# SCH_d_01_e_03.net
KiCad netlist of a schematic drawn in EasyEDA
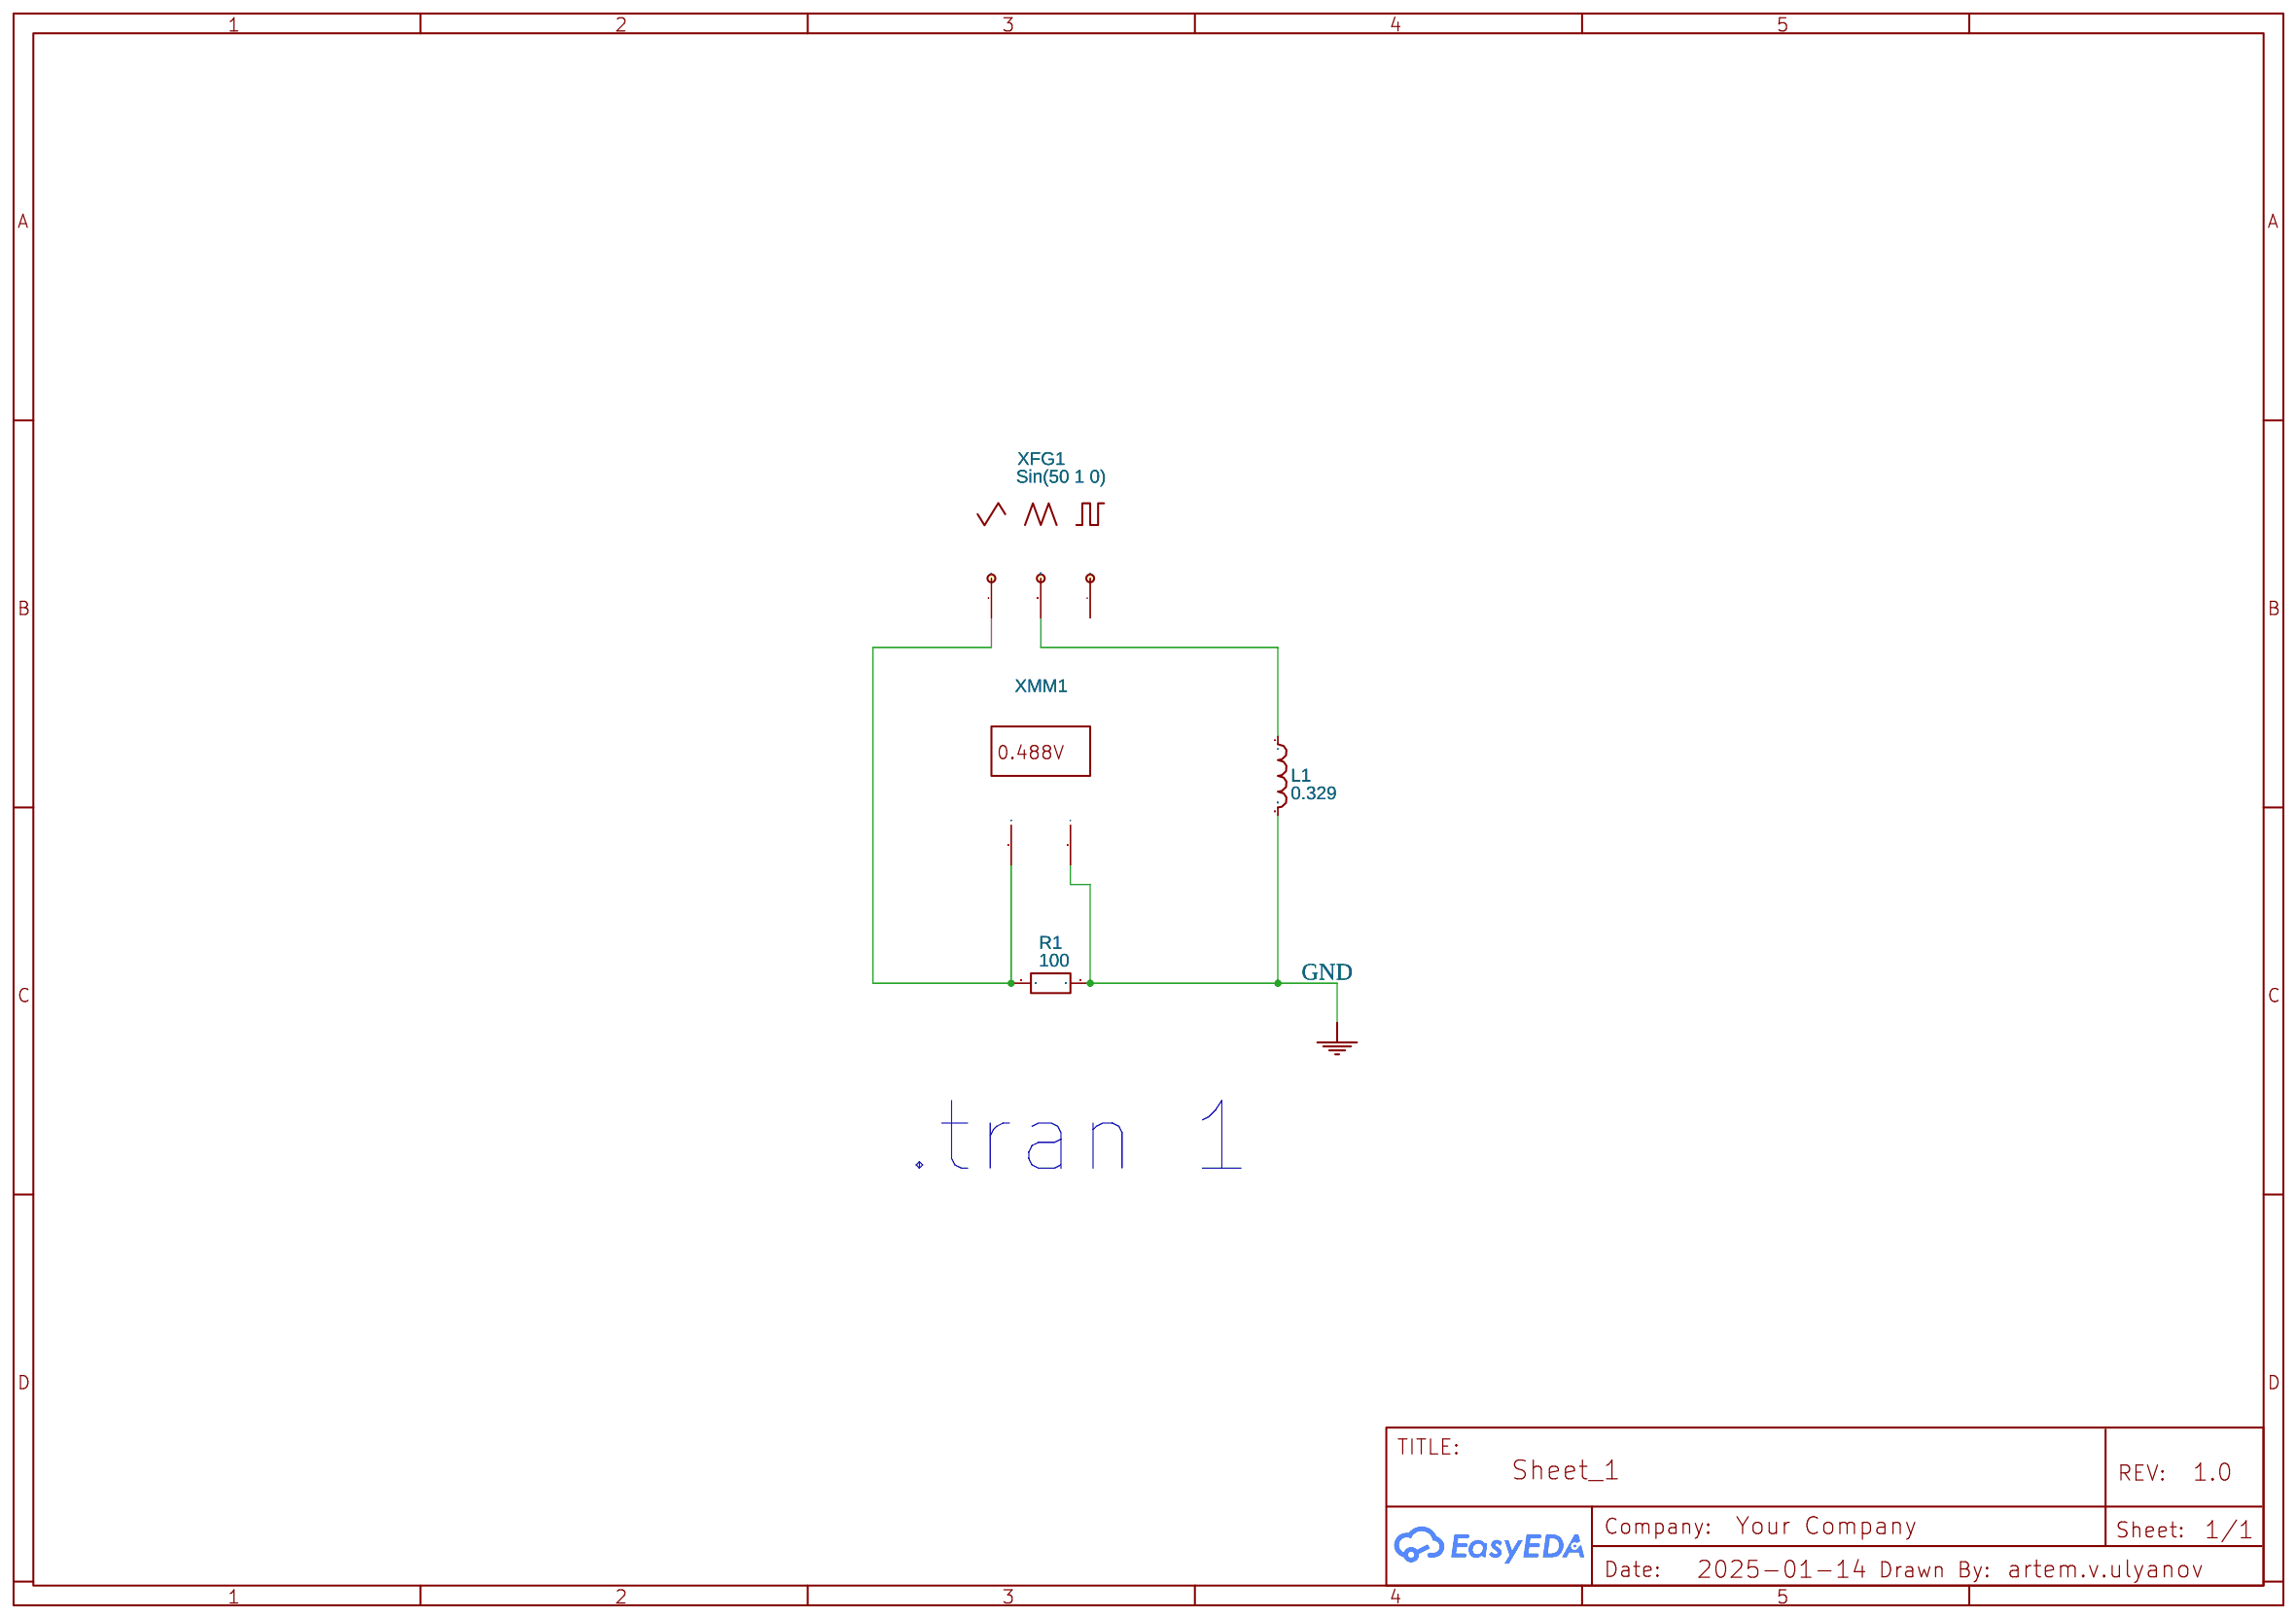
[diagram p0: schematic sheet]

(export (version "E")
  (design (tool "Eeschema 10.0.6"))
  (components
    (comp (ref "L1") (value "0.329") (libsource (lib "") (part "Inductor")))
    (comp (ref "R1") (value "100") (libsource (lib "") (part "R_0603_EU")))
    (comp (ref "XFG1") (value "Sin(50 1 0)") (libsource (lib "") (part "FUNCTIONGENERATOR")))
    (comp (ref "XMM1") (value "Multimeter") (libsource (lib "") (part "MULTIMETER")))
  )
  (nets
    (net (code "1") (name "GND") (class "Default")
      (node (ref "L1") (pin "2") (pinfunction "2_2") (pintype "unspecified"))
      (node (ref "R1") (pin "2") (pinfunction "2_2") (pintype "unspecified"))
      (node (ref "XMM1") (pin "2") (pinfunction "I_2") (pintype "unspecified"))
    )
    (net (code "2") (name "Net-(L1-Pad1)") (class "Default")
      (node (ref "L1") (pin "1") (pinfunction "1_1") (pintype "unspecified"))
      (node (ref "XFG1") (pin "COM") (pinfunction "COM_COM") (pintype "unspecified"))
    )
    (net (code "3") (name "Net-(XMM1-+)") (class "Default")
      (node (ref "R1") (pin "1") (pinfunction "1_1") (pintype "unspecified"))
      (node (ref "XFG1") (pin "+") (pinfunction "+_+") (pintype "unspecified"))
      (node (ref "XMM1") (pin "1") (pinfunction "+_1") (pintype "unspecified"))
    )
    (net (code "4") (name "unconnected-(XFG1-Pad-)") (class "Default")
      (node (ref "XFG1") (pin "-") (pinfunction "-_-") (pintype "unspecified"))
    )
  )
)
